# Transmitter.net
KiCad netlist of a schematic drawn in EAGLE
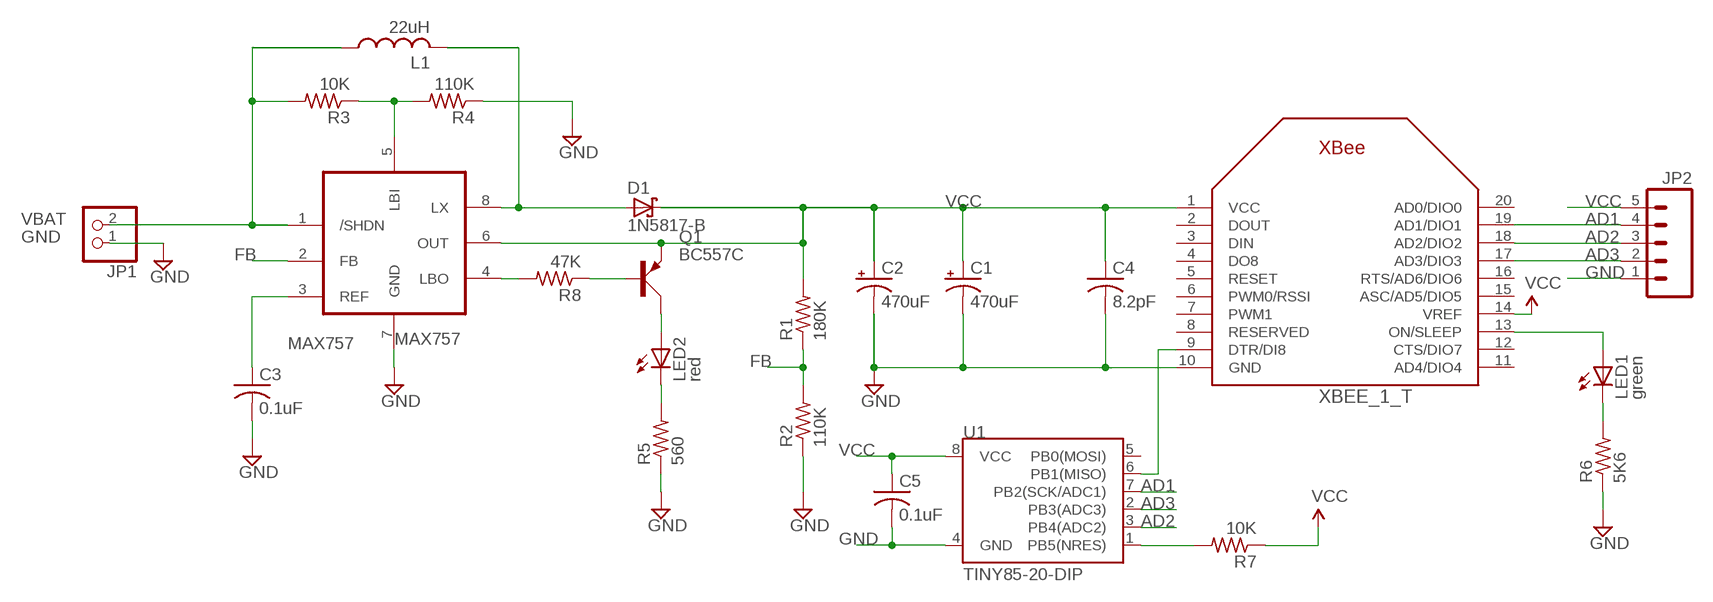
[diagram p0: schematic, sheet 1]

(export (version "E")
  (design (tool "Eeschema 10.0.6"))
  (components
    (comp (ref "C1")
      (value "470uF")
      (footprint "eagle-import:E3,5-8")
      (libsource (lib "eagle-import") (part "CPOL-USE3.5-8"))
    )
    (comp (ref "C2")
      (value "470uF")
      (footprint "eagle-import:E3,5-8")
      (libsource (lib "eagle-import") (part "CPOL-USE3.5-8"))
    )
    (comp (ref "C3")
      (value "0.1uF")
      (footprint "eagle-import:C025-024X044")
      (libsource (lib "eagle-import") (part "C-US025-024X044"))
    )
    (comp (ref "C4")
      (value "8.2pF")
      (footprint "eagle-import:C025-024X044")
      (libsource (lib "eagle-import") (part "C-US025-024X044"))
    )
    (comp (ref "C5")
      (value "0.1uF")
      (footprint "eagle-import:C025-024X044")
      (libsource (lib "eagle-import") (part "C-US025-024X044"))
    )
    (comp (ref "D1")
      (value "1N5817-B")
      (footprint "eagle-import:DO41-7.6")
      (libsource (lib "eagle-import") (part "1N5817-B"))
    )
    (comp (ref "JP1")
      (value "PINHD-1X2")
      (footprint "eagle-import:1X02")
      (libsource (lib "eagle-import") (part "PINHD-1X2"))
    )
    (comp (ref "JP2")
      (value "M05PTH")
      (footprint "eagle-import:1X05")
      (libsource (lib "eagle-import") (part "M05PTH"))
    )
    (comp (ref "L1")
      (value "22uH")
      (footprint "eagle-import:22R223C")
      (libsource (lib "eagle-import") (part "22R223C"))
    )
    (comp (ref "LED1")
      (value "green")
      (footprint "eagle-import:LED3MM")
      (libsource (lib "eagle-import") (part "LED3MM"))
    )
    (comp (ref "LED2")
      (value "red")
      (footprint "eagle-import:LED3MM")
      (libsource (lib "eagle-import") (part "LED3MM"))
    )
    (comp (ref "MAX757")
      (value "MAX757")
      (footprint "eagle-import:DIL08")
      (libsource (lib "eagle-import") (part "MAX757"))
    )
    (comp (ref "Q1")
      (value "BC557C")
      (footprint "eagle-import:TO92D")
      (libsource (lib "eagle-import") (part "BC557C"))
    )
    (comp (ref "R1")
      (value "180K")
      (footprint "eagle-import:0207_10")
      (libsource (lib "eagle-import") (part "resistor_R-US_0207/10"))
    )
    (comp (ref "R2")
      (value "110K")
      (footprint "eagle-import:0207_10")
      (libsource (lib "eagle-import") (part "resistor_R-US_0207/10"))
    )
    (comp (ref "R3")
      (value "10K")
      (footprint "eagle-import:0207_10")
      (libsource (lib "eagle-import") (part "R-US_0207/10"))
    )
    (comp (ref "R4")
      (value "110K")
      (footprint "eagle-import:0207_10")
      (libsource (lib "eagle-import") (part "resistor_R-US_0207/10"))
    )
    (comp (ref "R5")
      (value "560")
      (footprint "eagle-import:0207_10")
      (libsource (lib "eagle-import") (part "resistor_R-US_0207/10"))
    )
    (comp (ref "R6")
      (value "5K6")
      (footprint "eagle-import:0207_10")
      (libsource (lib "eagle-import") (part "R-US_0207/10"))
    )
    (comp (ref "R7")
      (value "10K")
      (footprint "eagle-import:0207_10")
      (libsource (lib "eagle-import") (part "R-US_0207/10"))
    )
    (comp (ref "R8")
      (value "47K")
      (footprint "eagle-import:0207_10")
      (libsource (lib "eagle-import") (part "resistor_R-US_0207/10"))
    )
    (comp (ref "U1")
      (value "TINY85-20-DIP")
      (footprint "eagle-import:DIP08")
      (libsource (lib "eagle-import") (part "ATTINY45TINY85-20-DIP"))
    )
    (comp (ref "XBEE_1_T")
      (value "XBEE")
      (footprint "eagle-import:XBEE")
      (libsource (lib "eagle-import") (part "XBEE"))
    )
  )
  (nets
    (net (code "1") (name "/AD1") (class "Default")
      (node (ref "JP2") (pin "4") (pinfunction "4_4") (pintype "passive"))
      (node (ref "U1") (pin "7") (pinfunction "PB2(SCK/ADC1)_7") (pintype "bidirectional"))
      (node (ref "XBEE_1_T") (pin "19") (pinfunction "AD1/DIO1_19") (pintype "bidirectional"))
    )
    (net (code "2") (name "/AD2") (class "Default")
      (node (ref "JP2") (pin "3") (pinfunction "3_3") (pintype "passive"))
      (node (ref "U1") (pin "3") (pinfunction "PB4(ADC2)_3") (pintype "bidirectional"))
      (node (ref "XBEE_1_T") (pin "18") (pinfunction "AD2/DIO2_18") (pintype "bidirectional"))
    )
    (net (code "3") (name "/AD3") (class "Default")
      (node (ref "JP2") (pin "2") (pinfunction "2_2") (pintype "passive"))
      (node (ref "U1") (pin "2") (pinfunction "PB3(ADC3)_2") (pintype "bidirectional"))
      (node (ref "XBEE_1_T") (pin "17") (pinfunction "AD3/DIO3_17") (pintype "bidirectional"))
    )
    (net (code "4") (name "/FB") (class "Default")
      (node (ref "MAX757") (pin "2") (pinfunction "FB_2") (pintype "bidirectional"))
      (node (ref "R1") (pin "1") (pinfunction "1_1") (pintype "passive"))
      (node (ref "R2") (pin "2") (pinfunction "2_2") (pintype "passive"))
    )
    (net (code "5") (name "/VBAT") (class "Default")
      (node (ref "JP1") (pin "2") (pinfunction "2_2") (pintype "passive"))
      (node (ref "L1") (pin "P$1") (pinfunction "1_P$1") (pintype "passive"))
      (node (ref "MAX757") (pin "1") (pinfunction "/SHDN_1") (pintype "input"))
      (node (ref "R3") (pin "2") (pinfunction "2_2") (pintype "passive"))
    )
    (net (code "6") (name "GND") (class "Default")
      (node (ref "C1") (pin "-") (pinfunction "-_-") (pintype "passive"))
      (node (ref "C2") (pin "-") (pinfunction "-_-") (pintype "passive"))
      (node (ref "C3") (pin "2") (pinfunction "2_2") (pintype "passive"))
      (node (ref "C4") (pin "2") (pinfunction "2_2") (pintype "passive"))
      (node (ref "C5") (pin "2") (pinfunction "2_2") (pintype "passive"))
      (node (ref "JP1") (pin "1") (pinfunction "1_1") (pintype "passive"))
      (node (ref "JP2") (pin "1") (pinfunction "1_1") (pintype "passive"))
      (node (ref "MAX757") (pin "7") (pinfunction "GND_7") (pintype "power_in"))
      (node (ref "R2") (pin "1") (pinfunction "1_1") (pintype "passive"))
      (node (ref "R4") (pin "1") (pinfunction "1_1") (pintype "passive"))
      (node (ref "R5") (pin "1") (pinfunction "1_1") (pintype "passive"))
      (node (ref "R6") (pin "1") (pinfunction "1_1") (pintype "passive"))
      (node (ref "U1") (pin "4") (pinfunction "GND_4") (pintype "bidirectional"))
      (node (ref "XBEE_1_T") (pin "10") (pinfunction "GND_10") (pintype "power_in"))
    )
    (net (code "7") (name "Net-(L1-2)") (class "Default")
      (node (ref "D1") (pin "A") (pinfunction "A_A") (pintype "passive"))
      (node (ref "L1") (pin "P$2") (pinfunction "2_P$2") (pintype "passive"))
      (node (ref "MAX757") (pin "8") (pinfunction "LX_8") (pintype "output"))
    )
    (net (code "8") (name "Net-(LED1-C)") (class "Default")
      (node (ref "LED1") (pin "K") (pinfunction "C_K") (pintype "passive"))
      (node (ref "R6") (pin "2") (pinfunction "2_2") (pintype "passive"))
    )
    (net (code "9") (name "Net-(LED2-C)") (class "Default")
      (node (ref "LED2") (pin "K") (pinfunction "C_K") (pintype "passive"))
      (node (ref "R5") (pin "2") (pinfunction "2_2") (pintype "passive"))
    )
    (net (code "10") (name "Net-(LED2-PadA)") (class "Default")
      (node (ref "LED2") (pin "A") (pinfunction "A_A") (pintype "passive"))
      (node (ref "Q1") (pin "C") (pinfunction "C_C") (pintype "passive"))
    )
    (net (code "11") (name "Net-(MAX757-LBI)") (class "Default")
      (node (ref "MAX757") (pin "5") (pinfunction "LBI_5") (pintype "input"))
      (node (ref "R3") (pin "1") (pinfunction "1_1") (pintype "passive"))
      (node (ref "R4") (pin "2") (pinfunction "2_2") (pintype "passive"))
    )
    (net (code "12") (name "Net-(MAX757-LBO)") (class "Default")
      (node (ref "MAX757") (pin "4") (pinfunction "LBO_4") (pintype "input"))
      (node (ref "R8") (pin "2") (pinfunction "2_2") (pintype "passive"))
    )
    (net (code "13") (name "Net-(MAX757-REF)") (class "Default")
      (node (ref "C3") (pin "1") (pinfunction "1_1") (pintype "passive"))
      (node (ref "MAX757") (pin "3") (pinfunction "REF_3") (pintype "passive"))
    )
    (net (code "14") (name "Net-(Q1-PadB)") (class "Default")
      (node (ref "Q1") (pin "B") (pinfunction "B_B") (pintype "passive"))
      (node (ref "R8") (pin "1") (pinfunction "1_1") (pintype "passive"))
    )
    (net (code "15") (name "Net-(U1-PB1(MISO))") (class "Default")
      (node (ref "U1") (pin "6") (pinfunction "PB1(MISO)_6") (pintype "bidirectional"))
      (node (ref "XBEE_1_T") (pin "9") (pinfunction "DTR/DI8_9") (pintype "input"))
    )
    (net (code "16") (name "Net-(U1-PB5(NRES))") (class "Default")
      (node (ref "R7") (pin "2") (pinfunction "2_2") (pintype "passive"))
      (node (ref "U1") (pin "1") (pinfunction "PB5(NRES)_1") (pintype "bidirectional"))
    )
    (net (code "17") (name "Net-(XBEE_1_T-ON{slash}SLEEP)") (class "Default")
      (node (ref "LED1") (pin "A") (pinfunction "A_A") (pintype "passive"))
      (node (ref "XBEE_1_T") (pin "13") (pinfunction "ON/SLEEP_13") (pintype "output"))
    )
    (net (code "18") (name "VCC") (class "Default")
      (node (ref "C1") (pin "+") (pinfunction "+_+") (pintype "passive"))
      (node (ref "C2") (pin "+") (pinfunction "+_+") (pintype "passive"))
      (node (ref "C4") (pin "1") (pinfunction "1_1") (pintype "passive"))
      (node (ref "C5") (pin "1") (pinfunction "1_1") (pintype "passive"))
      (node (ref "D1") (pin "C") (pinfunction "C_C") (pintype "passive"))
      (node (ref "JP2") (pin "5") (pinfunction "5_5") (pintype "passive"))
      (node (ref "MAX757") (pin "6") (pinfunction "OUT_6") (pintype "output"))
      (node (ref "Q1") (pin "E") (pinfunction "E_E") (pintype "passive"))
      (node (ref "R1") (pin "2") (pinfunction "2_2") (pintype "passive"))
      (node (ref "R7") (pin "1") (pinfunction "1_1") (pintype "passive"))
      (node (ref "U1") (pin "8") (pinfunction "VCC_8") (pintype "bidirectional"))
      (node (ref "XBEE_1_T") (pin "1") (pinfunction "VCC_1") (pintype "power_in"))
      (node (ref "XBEE_1_T") (pin "14") (pinfunction "VREF_14") (pintype "input"))
    )
    (net (code "19") (name "unconnected-(U1-PB0(MOSI)-Pad5)") (class "Default")
      (node (ref "U1") (pin "5") (pinfunction "PB0(MOSI)_5") (pintype "bidirectional"))
    )
    (net (code "20") (name "unconnected-(XBEE_1_T-AD0{slash}DIO0-Pad20)") (class "Default")
      (node (ref "XBEE_1_T") (pin "20") (pinfunction "AD0/DIO0_20") (pintype "bidirectional"))
    )
    (net (code "21") (name "unconnected-(XBEE_1_T-AD4{slash}DIO4-Pad11)") (class "Default")
      (node (ref "XBEE_1_T") (pin "11") (pinfunction "AD4/DIO4_11") (pintype "bidirectional"))
    )
    (net (code "22") (name "unconnected-(XBEE_1_T-ASC{slash}AD5{slash}DIO5-Pad15)") (class "Default")
      (node (ref "XBEE_1_T") (pin "15") (pinfunction "ASC/AD5/DIO5_15") (pintype "bidirectional"))
    )
    (net (code "23") (name "unconnected-(XBEE_1_T-CTS{slash}DIO7-Pad12)") (class "Default")
      (node (ref "XBEE_1_T") (pin "12") (pinfunction "CTS/DIO7_12") (pintype "bidirectional"))
    )
    (net (code "24") (name "unconnected-(XBEE_1_T-DIN-Pad3)") (class "Default")
      (node (ref "XBEE_1_T") (pin "3") (pinfunction "DIN_3") (pintype "input"))
    )
    (net (code "25") (name "unconnected-(XBEE_1_T-DO8-Pad4)") (class "Default")
      (node (ref "XBEE_1_T") (pin "4") (pinfunction "DO8_4") (pintype "output"))
    )
    (net (code "26") (name "unconnected-(XBEE_1_T-DOUT-Pad2)") (class "Default")
      (node (ref "XBEE_1_T") (pin "2") (pinfunction "DOUT_2") (pintype "output"))
    )
    (net (code "27") (name "unconnected-(XBEE_1_T-PWM0{slash}RSSI-Pad6)") (class "Default")
      (node (ref "XBEE_1_T") (pin "6") (pinfunction "PWM0/RSSI_6") (pintype "output"))
    )
    (net (code "28") (name "unconnected-(XBEE_1_T-PWM1-Pad7)") (class "Default")
      (node (ref "XBEE_1_T") (pin "7") (pinfunction "PWM1_7") (pintype "output"))
    )
    (net (code "29") (name "unconnected-(XBEE_1_T-RESERVED-Pad8)") (class "Default")
      (node (ref "XBEE_1_T") (pin "8") (pinfunction "RESERVED_8") (pintype "no_connect"))
    )
    (net (code "30") (name "unconnected-(XBEE_1_T-RESET-Pad5)") (class "Default")
      (node (ref "XBEE_1_T") (pin "5") (pinfunction "RESET_5") (pintype "input"))
    )
    (net (code "31") (name "unconnected-(XBEE_1_T-RTS{slash}AD6{slash}DIO6-Pad16)") (class "Default")
      (node (ref "XBEE_1_T") (pin "16") (pinfunction "RTS/AD6/DIO6_16") (pintype "bidirectional"))
    )
  )
)
